# integrated.net
KiCad netlist of a schematic drawn in EAGLE
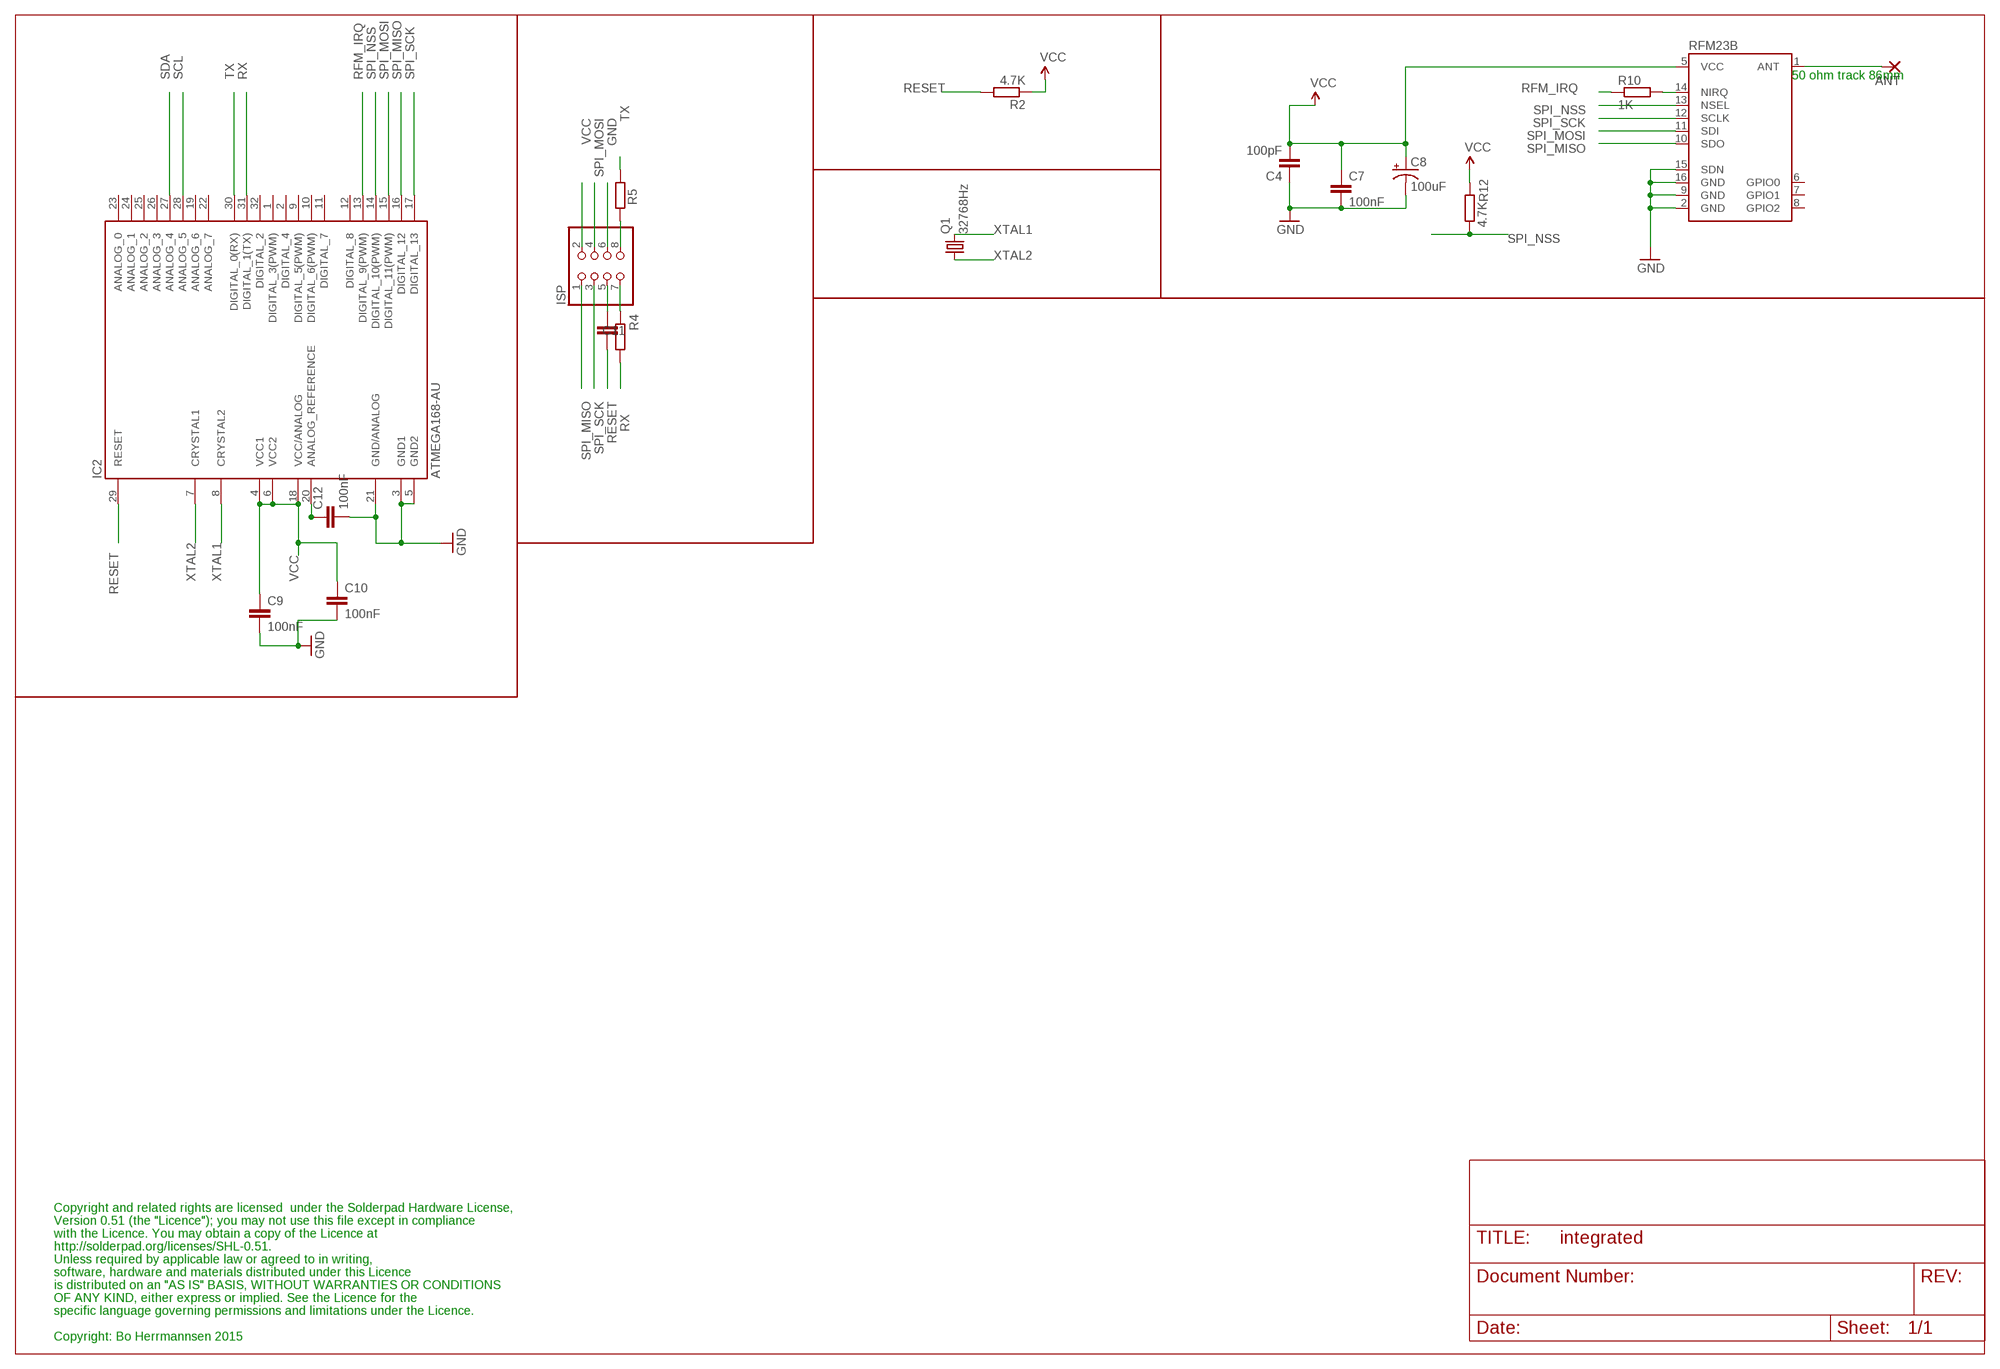
[diagram p0: schematic, sheet 1]

(export (version "E")
  (design (tool "Eeschema 10.0.6"))
  (components
    (comp (ref "ANT")
      (value "2,15/1,0")
      (footprint "eagle-import:2,15_1,0")
      (libsource (lib "eagle-import") (part "2,15/1,0"))
    )
    (comp (ref "C4")
      (value "100pF")
      (footprint "eagle-import:C0603")
      (libsource (lib "eagle-import") (part "C-EUC0603"))
    )
    (comp (ref "C7")
      (value "100nF")
      (footprint "eagle-import:C0603")
      (libsource (lib "eagle-import") (part "C-EUC0603"))
    )
    (comp (ref "C8")
      (value "100uF")
      (footprint "eagle-import:EIA3216")
      (libsource (lib "eagle-import") (part "CAP_POL1206"))
    )
    (comp (ref "C9")
      (value "100nF")
      (footprint "eagle-import:C0603")
      (libsource (lib "eagle-import") (part "C-EUC0603"))
    )
    (comp (ref "C10")
      (value "100nF")
      (footprint "eagle-import:C0603")
      (libsource (lib "eagle-import") (part "C-EUC0603"))
    )
    (comp (ref "C11")
      (value "100nF")
      (footprint "eagle-import:C0603")
      (libsource (lib "eagle-import") (part "C-EUC0603"))
    )
    (comp (ref "C12")
      (value "100nF")
      (footprint "eagle-import:C0603")
      (libsource (lib "eagle-import") (part "C-EUC0603"))
    )
    (comp (ref "IC2")
      (value "ATMEGA168-AU")
      (footprint "eagle-import:TQFP32-08")
      (libsource (lib "eagle-import") (part "ATMEGA168-AU"))
    )
    (comp (ref "ISP")
      (value "PINHD-2X4/90")
      (footprint "eagle-import:2X04_90")
      (libsource (lib "eagle-import") (part "PINHD-2X4/90"))
    )
    (comp (ref "Q1")
      (value "32768Hz")
      (footprint "eagle-import:MC-306")
      (fields (field (name "MPN") "MC-306 60.0KHZ  100PPM ,12.5PF"))
      (libsource (lib "eagle-import") (part "MC-306"))
    )
    (comp (ref "R2")
      (value "4.7K")
      (footprint "eagle-import:R0603")
      (libsource (lib "eagle-import") (part "R-EU_R0603"))
    )
    (comp (ref "R4")
      (value "4.7K")
      (footprint "eagle-import:R0603")
      (libsource (lib "eagle-import") (part "R-EU_R0603"))
    )
    (comp (ref "R5")
      (value "4.7K")
      (footprint "eagle-import:R0603")
      (libsource (lib "eagle-import") (part "R-EU_R0603"))
    )
    (comp (ref "R10")
      (value "1K")
      (footprint "eagle-import:R0603")
      (libsource (lib "eagle-import") (part "R-EU_R0603"))
    )
    (comp (ref "R12")
      (value "4.7K")
      (footprint "eagle-import:R0603")
      (libsource (lib "eagle-import") (part "R-EU_R0603"))
    )
    (comp (ref "RFM23B")
      (value "RFM23B")
      (footprint "eagle-import:RFM23-XXX-S1")
      (libsource (lib "eagle-import") (part "RFM23B"))
    )
  )
  (nets
    (net (code "1") (name "/RESET") (class "Default")
      (node (ref "C11") (pin "1") (pinfunction "1_1") (pintype "passive"))
      (node (ref "IC2") (pin "29") (pinfunction "RESET_29") (pintype "bidirectional"))
      (node (ref "R2") (pin "2") (pinfunction "2_2") (pintype "passive"))
    )
    (net (code "2") (name "/RFM_IRQ") (class "Default")
      (node (ref "IC2") (pin "13") (pinfunction "DIGITAL_9(PWM)_13") (pintype "bidirectional"))
      (node (ref "R10") (pin "1") (pinfunction "1_1") (pintype "passive"))
    )
    (net (code "3") (name "/RX") (class "Default")
      (node (ref "IC2") (pin "31") (pinfunction "DIGITAL_1(TX)_31") (pintype "bidirectional"))
      (node (ref "R4") (pin "1") (pinfunction "1_1") (pintype "passive"))
    )
    (net (code "4") (name "/SCL") (class "Default")
      (node (ref "IC2") (pin "28") (pinfunction "ANALOG_5_28") (pintype "bidirectional"))
    )
    (net (code "5") (name "/SDA") (class "Default")
      (node (ref "IC2") (pin "27") (pinfunction "ANALOG_4_27") (pintype "bidirectional"))
    )
    (net (code "6") (name "/SPI_MISO") (class "Default")
      (node (ref "IC2") (pin "16") (pinfunction "DIGITAL_12_16") (pintype "bidirectional"))
      (node (ref "ISP") (pin "1") (pinfunction "1_1") (pintype "passive"))
      (node (ref "RFM23B") (pin "10") (pinfunction "SDO_10") (pintype "output"))
    )
    (net (code "7") (name "/SPI_MOSI") (class "Default")
      (node (ref "IC2") (pin "15") (pinfunction "DIGITAL_11(PWM)_15") (pintype "bidirectional"))
      (node (ref "ISP") (pin "4") (pinfunction "4_4") (pintype "passive"))
      (node (ref "RFM23B") (pin "11") (pinfunction "SDI_11") (pintype "input"))
    )
    (net (code "8") (name "/SPI_NSS") (class "Default")
      (node (ref "IC2") (pin "14") (pinfunction "DIGITAL_10(PWM)_14") (pintype "bidirectional"))
      (node (ref "R12") (pin "1") (pinfunction "1_1") (pintype "passive"))
      (node (ref "RFM23B") (pin "13") (pinfunction "NSEL_13") (pintype "input"))
    )
    (net (code "9") (name "/SPI_SCK") (class "Default")
      (node (ref "IC2") (pin "17") (pinfunction "DIGITAL_13_17") (pintype "bidirectional"))
      (node (ref "ISP") (pin "3") (pinfunction "3_3") (pintype "passive"))
      (node (ref "RFM23B") (pin "12") (pinfunction "SCLK_12") (pintype "input"))
    )
    (net (code "10") (name "/TX") (class "Default")
      (node (ref "IC2") (pin "30") (pinfunction "DIGITAL_0(RX)_30") (pintype "bidirectional"))
      (node (ref "R5") (pin "1") (pinfunction "1_1") (pintype "passive"))
    )
    (net (code "11") (name "/XTAL1") (class "Default")
      (node (ref "IC2") (pin "8") (pinfunction "CRYSTAL2_8") (pintype "bidirectional"))
      (node (ref "Q1") (pin "4") (pinfunction "2_4") (pintype "passive"))
    )
    (net (code "12") (name "/XTAL2") (class "Default")
      (node (ref "IC2") (pin "7") (pinfunction "CRYSTAL1_7") (pintype "bidirectional"))
      (node (ref "Q1") (pin "1") (pinfunction "1_1") (pintype "passive"))
    )
    (net (code "13") (name "GND") (class "Default")
      (node (ref "C10") (pin "2") (pinfunction "2_2") (pintype "passive"))
      (node (ref "C12") (pin "2") (pinfunction "2_2") (pintype "passive"))
      (node (ref "C4") (pin "1") (pinfunction "1_1") (pintype "passive"))
      (node (ref "C7") (pin "2") (pinfunction "2_2") (pintype "passive"))
      (node (ref "C8") (pin "C") (pinfunction "-_C") (pintype "passive"))
      (node (ref "C9") (pin "2") (pinfunction "2_2") (pintype "passive"))
      (node (ref "IC2") (pin "21") (pinfunction "GND/ANALOG_21") (pintype "power_in"))
      (node (ref "IC2") (pin "3") (pinfunction "GND1_3") (pintype "power_in"))
      (node (ref "IC2") (pin "5") (pinfunction "GND2_5") (pintype "power_in"))
      (node (ref "ISP") (pin "6") (pinfunction "6_6") (pintype "passive"))
      (node (ref "RFM23B") (pin "15") (pinfunction "SDN_15") (pintype "input"))
      (node (ref "RFM23B") (pin "16") (pinfunction "GND_16") (pintype "power_in"))
      (node (ref "RFM23B") (pin "2") (pinfunction "GND_2") (pintype "power_in"))
      (node (ref "RFM23B") (pin "9") (pinfunction "GND_9") (pintype "power_in"))
    )
    (net (code "14") (name "Net-(ANT-P)") (class "Default")
      (node (ref "ANT") (pin "1") (pinfunction "P_1") (pintype "passive"))
      (node (ref "RFM23B") (pin "1") (pinfunction "ANT_1") (pintype "bidirectional"))
    )
    (net (code "15") (name "Net-(C11-Pad2)") (class "Default")
      (node (ref "C11") (pin "2") (pinfunction "2_2") (pintype "passive"))
      (node (ref "ISP") (pin "5") (pinfunction "5_5") (pintype "passive"))
    )
    (net (code "16") (name "Net-(IC2-ANALOG_REFERENCE)") (class "Default")
      (node (ref "C12") (pin "1") (pinfunction "1_1") (pintype "passive"))
      (node (ref "IC2") (pin "20") (pinfunction "ANALOG_REFERENCE_20") (pintype "passive"))
    )
    (net (code "17") (name "Net-(ISP-Pad7)") (class "Default")
      (node (ref "ISP") (pin "7") (pinfunction "7_7") (pintype "passive"))
      (node (ref "R4") (pin "2") (pinfunction "2_2") (pintype "passive"))
    )
    (net (code "18") (name "Net-(ISP-Pad8)") (class "Default")
      (node (ref "ISP") (pin "8") (pinfunction "8_8") (pintype "passive"))
      (node (ref "R5") (pin "2") (pinfunction "2_2") (pintype "passive"))
    )
    (net (code "19") (name "Net-(RFM23B-NIRQ)") (class "Default")
      (node (ref "R10") (pin "2") (pinfunction "2_2") (pintype "passive"))
      (node (ref "RFM23B") (pin "14") (pinfunction "NIRQ_14") (pintype "output"))
    )
    (net (code "20") (name "VCC") (class "Default")
      (node (ref "C10") (pin "1") (pinfunction "1_1") (pintype "passive"))
      (node (ref "C4") (pin "2") (pinfunction "2_2") (pintype "passive"))
      (node (ref "C7") (pin "1") (pinfunction "1_1") (pintype "passive"))
      (node (ref "C8") (pin "A") (pinfunction "+_A") (pintype "passive"))
      (node (ref "C9") (pin "1") (pinfunction "1_1") (pintype "passive"))
      (node (ref "IC2") (pin "18") (pinfunction "VCC/ANALOG_18") (pintype "passive"))
      (node (ref "IC2") (pin "4") (pinfunction "VCC1_4") (pintype "power_in"))
      (node (ref "IC2") (pin "6") (pinfunction "VCC2_6") (pintype "power_in"))
      (node (ref "ISP") (pin "2") (pinfunction "2_2") (pintype "passive"))
      (node (ref "R12") (pin "2") (pinfunction "2_2") (pintype "passive"))
      (node (ref "R2") (pin "1") (pinfunction "1_1") (pintype "passive"))
      (node (ref "RFM23B") (pin "5") (pinfunction "VCC_5") (pintype "bidirectional"))
    )
    (net (code "21") (name "unconnected-(IC2-ANALOG_0-Pad23)") (class "Default")
      (node (ref "IC2") (pin "23") (pinfunction "ANALOG_0_23") (pintype "bidirectional"))
    )
    (net (code "22") (name "unconnected-(IC2-ANALOG_1-Pad24)") (class "Default")
      (node (ref "IC2") (pin "24") (pinfunction "ANALOG_1_24") (pintype "bidirectional"))
    )
    (net (code "23") (name "unconnected-(IC2-ANALOG_2-Pad25)") (class "Default")
      (node (ref "IC2") (pin "25") (pinfunction "ANALOG_2_25") (pintype "bidirectional"))
    )
    (net (code "24") (name "unconnected-(IC2-ANALOG_3-Pad26)") (class "Default")
      (node (ref "IC2") (pin "26") (pinfunction "ANALOG_3_26") (pintype "bidirectional"))
    )
    (net (code "25") (name "unconnected-(IC2-ANALOG_6-Pad19)") (class "Default")
      (node (ref "IC2") (pin "19") (pinfunction "ANALOG_6_19") (pintype "passive"))
    )
    (net (code "26") (name "unconnected-(IC2-ANALOG_7-Pad22)") (class "Default")
      (node (ref "IC2") (pin "22") (pinfunction "ANALOG_7_22") (pintype "passive"))
    )
    (net (code "27") (name "unconnected-(IC2-DIGITAL_2-Pad32)") (class "Default")
      (node (ref "IC2") (pin "32") (pinfunction "DIGITAL_2_32") (pintype "bidirectional"))
    )
    (net (code "28") (name "unconnected-(IC2-DIGITAL_3(PWM)-Pad1)") (class "Default")
      (node (ref "IC2") (pin "1") (pinfunction "DIGITAL_3(PWM)_1") (pintype "bidirectional"))
    )
    (net (code "29") (name "unconnected-(IC2-DIGITAL_4-Pad2)") (class "Default")
      (node (ref "IC2") (pin "2") (pinfunction "DIGITAL_4_2") (pintype "bidirectional"))
    )
    (net (code "30") (name "unconnected-(IC2-DIGITAL_5(PWM)-Pad9)") (class "Default")
      (node (ref "IC2") (pin "9") (pinfunction "DIGITAL_5(PWM)_9") (pintype "bidirectional"))
    )
    (net (code "31") (name "unconnected-(IC2-DIGITAL_6(PWM)-Pad10)") (class "Default")
      (node (ref "IC2") (pin "10") (pinfunction "DIGITAL_6(PWM)_10") (pintype "bidirectional"))
    )
    (net (code "32") (name "unconnected-(IC2-DIGITAL_7-Pad11)") (class "Default")
      (node (ref "IC2") (pin "11") (pinfunction "DIGITAL_7_11") (pintype "bidirectional"))
    )
    (net (code "33") (name "unconnected-(IC2-DIGITAL_8-Pad12)") (class "Default")
      (node (ref "IC2") (pin "12") (pinfunction "DIGITAL_8_12") (pintype "bidirectional"))
    )
    (net (code "34") (name "unconnected-(RFM23B-GPIO0-Pad6)") (class "Default")
      (node (ref "RFM23B") (pin "6") (pinfunction "GPIO0_6") (pintype "bidirectional"))
    )
    (net (code "35") (name "unconnected-(RFM23B-GPIO1-Pad7)") (class "Default")
      (node (ref "RFM23B") (pin "7") (pinfunction "GPIO1_7") (pintype "bidirectional"))
    )
    (net (code "36") (name "unconnected-(RFM23B-GPIO2-Pad8)") (class "Default")
      (node (ref "RFM23B") (pin "8") (pinfunction "GPIO2_8") (pintype "bidirectional"))
    )
  )
)
